# Lemming2_sensors.net
KiCad netlist of a schematic drawn in EAGLE
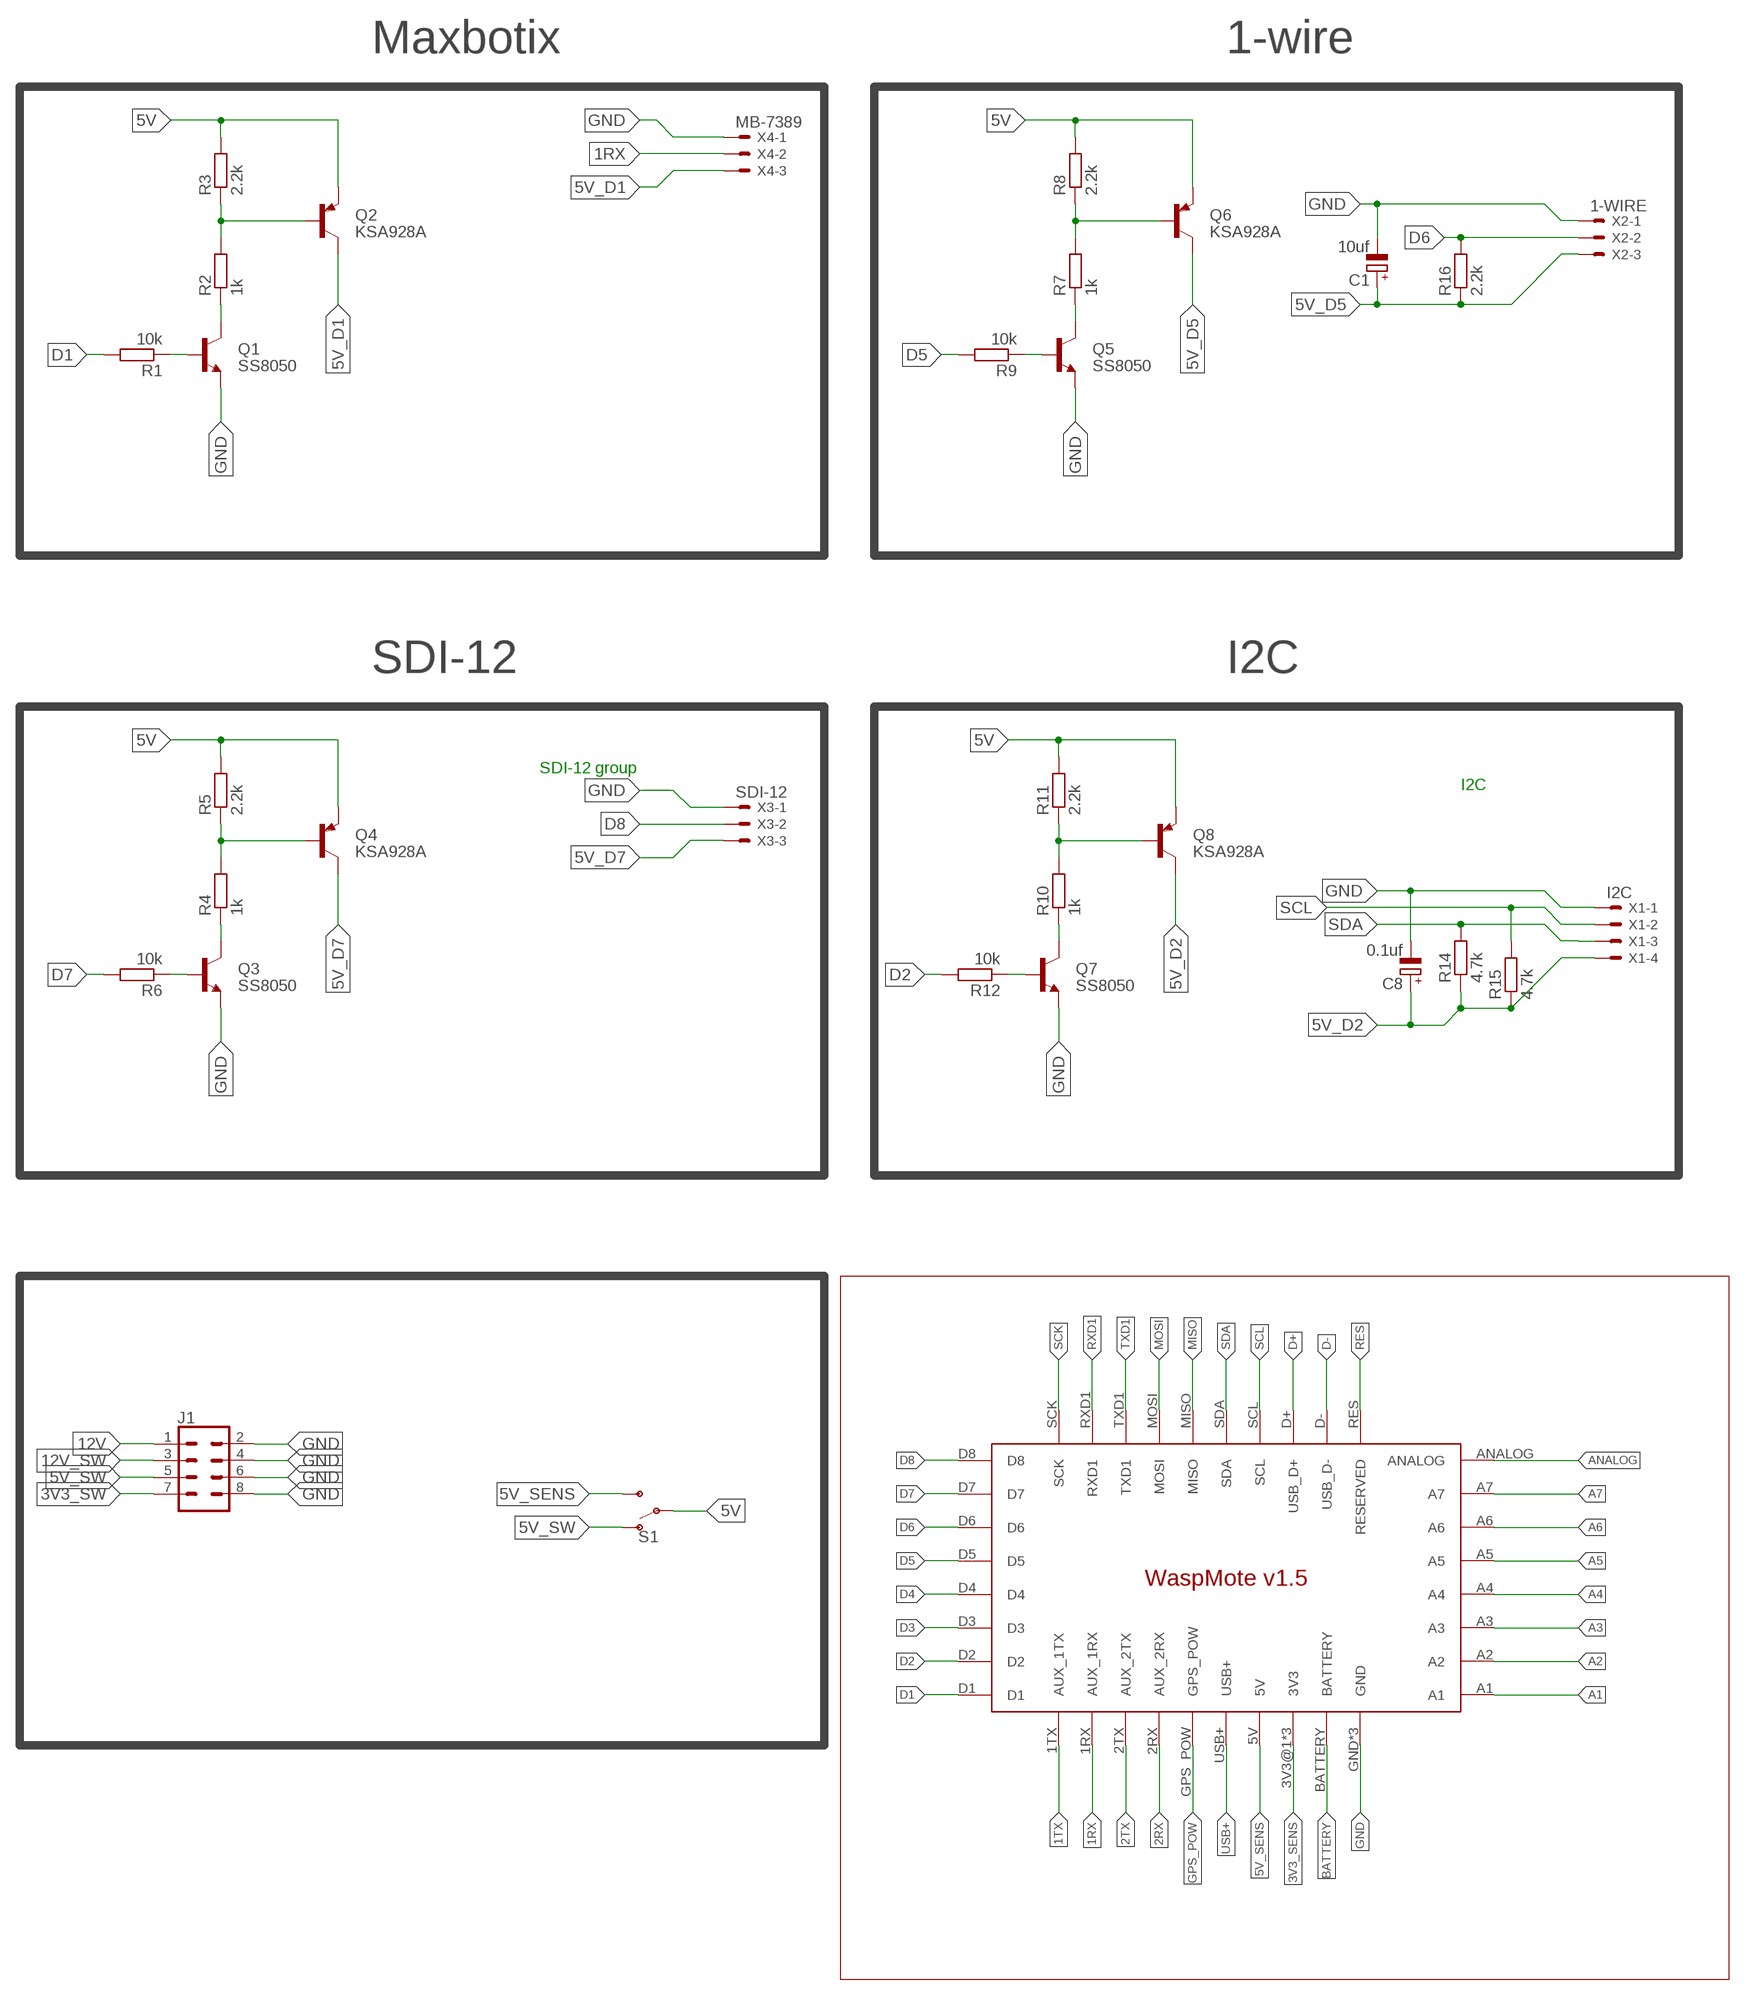
[diagram p0: schematic, sheet 1]

(export (version "E")
  (design (tool "Eeschema 10.0.6"))
  (components
    (comp (ref "C1")
      (value "10uf")
      (footprint "eagle-import:E2,5-5")
      (libsource (lib "eagle-import") (part "CPOL-EUE2.5-5"))
    )
    (comp (ref "C8")
      (value "0.1uf")
      (footprint "eagle-import:E2,5-5")
      (libsource (lib "eagle-import") (part "CPOL-EUE2.5-5"))
    )
    (comp (ref "J1")
      (value "CONN_04X2")
      (footprint "eagle-import:2X4")
      (libsource (lib "eagle-import") (part "CONN_04X2"))
    )
    (comp (ref "Q1")
      (value "SS8050")
      (footprint "eagle-import:TO-92-EBC")
      (libsource (lib "eagle-import") (part "SS8050"))
    )
    (comp (ref "Q2")
      (value "KSA928A")
      (footprint "eagle-import:TO-92-ECB")
      (libsource (lib "eagle-import") (part "KSA928A"))
    )
    (comp (ref "Q3")
      (value "SS8050")
      (footprint "eagle-import:TO-92-EBC")
      (libsource (lib "eagle-import") (part "SS8050"))
    )
    (comp (ref "Q4")
      (value "KSA928A")
      (footprint "eagle-import:TO-92-ECB")
      (libsource (lib "eagle-import") (part "KSA928A"))
    )
    (comp (ref "Q5")
      (value "SS8050")
      (footprint "eagle-import:TO-92-EBC")
      (libsource (lib "eagle-import") (part "SS8050"))
    )
    (comp (ref "Q6")
      (value "KSA928A")
      (footprint "eagle-import:TO-92-ECB")
      (libsource (lib "eagle-import") (part "KSA928A"))
    )
    (comp (ref "Q7")
      (value "SS8050")
      (footprint "eagle-import:TO-92-EBC")
      (libsource (lib "eagle-import") (part "SS8050"))
    )
    (comp (ref "Q8")
      (value "KSA928A")
      (footprint "eagle-import:TO-92-ECB")
      (libsource (lib "eagle-import") (part "KSA928A"))
    )
    (comp (ref "R1")
      (value "10k")
      (footprint "eagle-import:RESISTOR_0309_10")
      (libsource (lib "eagle-import") (part "RESISTOR_R-EU_0309/10"))
    )
    (comp (ref "R2")
      (value "1k")
      (footprint "eagle-import:RESISTOR_0309_10")
      (libsource (lib "eagle-import") (part "RESISTOR_R-EU_0309/10"))
    )
    (comp (ref "R3")
      (value "2.2k")
      (footprint "eagle-import:RESISTOR_0309_10")
      (libsource (lib "eagle-import") (part "RESISTOR_R-EU_0309/10"))
    )
    (comp (ref "R4")
      (value "1k")
      (footprint "eagle-import:RESISTOR_0309_10")
      (libsource (lib "eagle-import") (part "RESISTOR_R-EU_0309/10"))
    )
    (comp (ref "R5")
      (value "2.2k")
      (footprint "eagle-import:RESISTOR_0309_10")
      (libsource (lib "eagle-import") (part "RESISTOR_R-EU_0309/10"))
    )
    (comp (ref "R6")
      (value "10k")
      (footprint "eagle-import:RESISTOR_0309_10")
      (libsource (lib "eagle-import") (part "RESISTOR_R-EU_0309/10"))
    )
    (comp (ref "R7")
      (value "1k")
      (footprint "eagle-import:RESISTOR_0309_10")
      (libsource (lib "eagle-import") (part "RESISTOR_R-EU_0309/10"))
    )
    (comp (ref "R8")
      (value "2.2k")
      (footprint "eagle-import:RESISTOR_0309_10")
      (libsource (lib "eagle-import") (part "RESISTOR_R-EU_0309/10"))
    )
    (comp (ref "R9")
      (value "10k")
      (footprint "eagle-import:RESISTOR_0309_10")
      (libsource (lib "eagle-import") (part "RESISTOR_R-EU_0309/10"))
    )
    (comp (ref "R10")
      (value "1k")
      (footprint "eagle-import:RESISTOR_0309_10")
      (libsource (lib "eagle-import") (part "RESISTOR_R-EU_0309/10"))
    )
    (comp (ref "R11")
      (value "2.2k")
      (footprint "eagle-import:RESISTOR_0309_10")
      (libsource (lib "eagle-import") (part "RESISTOR_R-EU_0309/10"))
    )
    (comp (ref "R12")
      (value "10k")
      (footprint "eagle-import:RESISTOR_0309_10")
      (libsource (lib "eagle-import") (part "RESISTOR_R-EU_0309/10"))
    )
    (comp (ref "R14")
      (value "4.7k")
      (footprint "eagle-import:RESISTOR_0309_10")
      (libsource (lib "eagle-import") (part "RESISTOR_R-EU_0309/10"))
    )
    (comp (ref "R15")
      (value "4.7k")
      (footprint "eagle-import:RESISTOR_0309_10")
      (libsource (lib "eagle-import") (part "RESISTOR_R-EU_0309/10"))
    )
    (comp (ref "R16")
      (value "2.2k")
      (footprint "eagle-import:RESISTOR_0309_10")
      (libsource (lib "eagle-import") (part "RESISTOR_R-EU_0309/10"))
    )
    (comp (ref "S1")
      (value "SWITCH-SPDT-PTH-11.6X4.0MM")
      (footprint "eagle-import:SWITCH_SPDT_PTH_11.6X4.0MM")
      (libsource (lib "eagle-import") (part "SWITCH-SPDT-PTH-11.6X4.0MM"))
    )
    (comp (ref "U$1")
      (value "WASPMOTE_V1.5")
      (footprint "eagle-import:WASPMOTE_V1.5")
      (libsource (lib "eagle-import") (part "WASPMOTE_V1.5"))
    )
    (comp (ref "X1")
      (value "I2C")
      (footprint "eagle-import:22-23-2041")
      (fields (field (name "MF") "MOLEX") (field (name "MPN") "22-23-2041"))
      (libsource (lib "eagle-import") (part "22-23-2041"))
    )
    (comp (ref "X2")
      (value "1-WIRE")
      (footprint "eagle-import:22-23-2031")
      (fields (field (name "MF") "MOLEX") (field (name "MPN") "22-23-2031"))
      (libsource (lib "eagle-import") (part "22-23-2031"))
    )
    (comp (ref "X3")
      (value "SDI-12")
      (footprint "eagle-import:22-23-2031")
      (fields (field (name "MF") "MOLEX") (field (name "MPN") "22-23-2031"))
      (libsource (lib "eagle-import") (part "22-23-2031"))
    )
    (comp (ref "X4")
      (value "MB-7389")
      (footprint "eagle-import:22-23-2031")
      (fields (field (name "MF") "MOLEX") (field (name "MPN") "22-23-2031"))
      (libsource (lib "eagle-import") (part "22-23-2031"))
    )
  )
  (nets
    (net (code "1") (name "1RX") (class "Default")
      (node (ref "U$1") (pin "1RX") (pinfunction "AUX_1RX_1RX") (pintype "bidirectional"))
      (node (ref "X4") (pin "2") (pinfunction "S_2") (pintype "passive"))
    )
    (net (code "2") (name "1TX") (class "Default")
      (node (ref "U$1") (pin "1TX") (pinfunction "AUX_1TX_1TX") (pintype "bidirectional"))
    )
    (net (code "3") (name "2RX") (class "Default")
      (node (ref "U$1") (pin "2RX") (pinfunction "AUX_2RX_2RX") (pintype "bidirectional"))
    )
    (net (code "4") (name "2TX") (class "Default")
      (node (ref "U$1") (pin "2TX") (pinfunction "AUX_2TX_2TX") (pintype "bidirectional"))
    )
    (net (code "5") (name "3V3_SENS") (class "Default")
      (node (ref "U$1") (pin "3V3@1") (pinfunction "3V3_3V3@1") (pintype "bidirectional"))
      (node (ref "U$1") (pin "3V3@2") (pinfunction "3V3_3V3@2") (pintype "bidirectional"))
      (node (ref "U$1") (pin "3V3@3") (pinfunction "3V3_3V3@3") (pintype "bidirectional"))
    )
    (net (code "6") (name "3V3_SW") (class "Default")
      (node (ref "J1") (pin "7") (pinfunction "7_7") (pintype "passive"))
    )
    (net (code "7") (name "5V") (class "Default")
      (node (ref "Q2") (pin "E") (pinfunction "E_E") (pintype "passive"))
      (node (ref "Q4") (pin "E") (pinfunction "E_E") (pintype "passive"))
      (node (ref "Q6") (pin "E") (pinfunction "E_E") (pintype "passive"))
      (node (ref "Q8") (pin "E") (pinfunction "E_E") (pintype "passive"))
      (node (ref "R11") (pin "2") (pinfunction "2_2") (pintype "passive"))
      (node (ref "R3") (pin "2") (pinfunction "2_2") (pintype "passive"))
      (node (ref "R5") (pin "2") (pinfunction "2_2") (pintype "passive"))
      (node (ref "R8") (pin "2") (pinfunction "2_2") (pintype "passive"))
      (node (ref "S1") (pin "2") (pinfunction "P_2") (pintype "passive"))
    )
    (net (code "8") (name "5V_D1") (class "Default")
      (node (ref "Q2") (pin "C") (pinfunction "C_C") (pintype "passive"))
      (node (ref "X4") (pin "3") (pinfunction "S_3") (pintype "passive"))
    )
    (net (code "9") (name "5V_D2") (class "Default")
      (node (ref "C8") (pin "+") (pinfunction "+_+") (pintype "passive"))
      (node (ref "Q8") (pin "C") (pinfunction "C_C") (pintype "passive"))
      (node (ref "R14") (pin "1") (pinfunction "1_1") (pintype "passive"))
      (node (ref "R15") (pin "1") (pinfunction "1_1") (pintype "passive"))
      (node (ref "X1") (pin "4") (pinfunction "S_4") (pintype "passive"))
    )
    (net (code "10") (name "5V_D5") (class "Default")
      (node (ref "C1") (pin "+") (pinfunction "+_+") (pintype "passive"))
      (node (ref "Q6") (pin "C") (pinfunction "C_C") (pintype "passive"))
      (node (ref "R16") (pin "1") (pinfunction "1_1") (pintype "passive"))
      (node (ref "X2") (pin "3") (pinfunction "S_3") (pintype "passive"))
    )
    (net (code "11") (name "5V_D7") (class "Default")
      (node (ref "Q4") (pin "C") (pinfunction "C_C") (pintype "passive"))
      (node (ref "X3") (pin "3") (pinfunction "S_3") (pintype "passive"))
    )
    (net (code "12") (name "5V_SENS") (class "Default")
      (node (ref "S1") (pin "3") (pinfunction "S_3") (pintype "passive"))
      (node (ref "U$1") (pin "5V") (pinfunction "5V_5V") (pintype "bidirectional"))
    )
    (net (code "13") (name "5V_SW") (class "Default")
      (node (ref "J1") (pin "5") (pinfunction "5_5") (pintype "passive"))
      (node (ref "S1") (pin "1") (pinfunction "O_1") (pintype "passive"))
    )
    (net (code "14") (name "12V") (class "Default")
      (node (ref "J1") (pin "1") (pinfunction "1_1") (pintype "passive"))
    )
    (net (code "15") (name "12V_SW") (class "Default")
      (node (ref "J1") (pin "3") (pinfunction "3_3") (pintype "passive"))
    )
    (net (code "16") (name "A1") (class "Default")
      (node (ref "U$1") (pin "A1") (pinfunction "A1_A1") (pintype "bidirectional"))
    )
    (net (code "17") (name "A2") (class "Default")
      (node (ref "U$1") (pin "A2") (pinfunction "A2_A2") (pintype "bidirectional"))
    )
    (net (code "18") (name "A3") (class "Default")
      (node (ref "U$1") (pin "A3") (pinfunction "A3_A3") (pintype "bidirectional"))
    )
    (net (code "19") (name "A4") (class "Default")
      (node (ref "U$1") (pin "A4") (pinfunction "A4_A4") (pintype "bidirectional"))
    )
    (net (code "20") (name "A5") (class "Default")
      (node (ref "U$1") (pin "A5") (pinfunction "A5_A5") (pintype "bidirectional"))
    )
    (net (code "21") (name "A6") (class "Default")
      (node (ref "U$1") (pin "A6") (pinfunction "A6_A6") (pintype "bidirectional"))
    )
    (net (code "22") (name "A7") (class "Default")
      (node (ref "U$1") (pin "A7") (pinfunction "A7_A7") (pintype "bidirectional"))
    )
    (net (code "23") (name "ANALOG") (class "Default")
      (node (ref "U$1") (pin "ANALOG") (pinfunction "ANALOG_ANALOG") (pintype "bidirectional"))
    )
    (net (code "24") (name "BATTERY") (class "Default")
      (node (ref "U$1") (pin "BATTERY") (pinfunction "BATTERY_BATTERY") (pintype "bidirectional"))
    )
    (net (code "25") (name "D+") (class "Default")
      (node (ref "U$1") (pin "D+") (pinfunction "USB_D+_D+") (pintype "bidirectional"))
    )
    (net (code "26") (name "D-") (class "Default")
      (node (ref "U$1") (pin "D-") (pinfunction "USB_D-_D-") (pintype "bidirectional"))
    )
    (net (code "27") (name "D1") (class "Default")
      (node (ref "R1") (pin "2") (pinfunction "2_2") (pintype "passive"))
      (node (ref "U$1") (pin "D1") (pinfunction "D1_D1") (pintype "bidirectional"))
    )
    (net (code "28") (name "D2") (class "Default")
      (node (ref "R12") (pin "2") (pinfunction "2_2") (pintype "passive"))
      (node (ref "U$1") (pin "D2") (pinfunction "D2_D2") (pintype "bidirectional"))
    )
    (net (code "29") (name "D3") (class "Default")
      (node (ref "U$1") (pin "D3") (pinfunction "D3_D3") (pintype "bidirectional"))
    )
    (net (code "30") (name "D4") (class "Default")
      (node (ref "U$1") (pin "D4") (pinfunction "D4_D4") (pintype "bidirectional"))
    )
    (net (code "31") (name "D5") (class "Default")
      (node (ref "R9") (pin "2") (pinfunction "2_2") (pintype "passive"))
      (node (ref "U$1") (pin "D5") (pinfunction "D5_D5") (pintype "bidirectional"))
    )
    (net (code "32") (name "D6") (class "Default")
      (node (ref "R16") (pin "2") (pinfunction "2_2") (pintype "passive"))
      (node (ref "U$1") (pin "D6") (pinfunction "D6_D6") (pintype "bidirectional"))
      (node (ref "X2") (pin "2") (pinfunction "S_2") (pintype "passive"))
    )
    (net (code "33") (name "D7") (class "Default")
      (node (ref "R6") (pin "2") (pinfunction "2_2") (pintype "passive"))
      (node (ref "U$1") (pin "D7") (pinfunction "D7_D7") (pintype "bidirectional"))
    )
    (net (code "34") (name "D8") (class "Default")
      (node (ref "U$1") (pin "D8") (pinfunction "D8_D8") (pintype "bidirectional"))
      (node (ref "X3") (pin "2") (pinfunction "S_2") (pintype "passive"))
    )
    (net (code "35") (name "GND") (class "Default")
      (node (ref "C1") (pin "-") (pinfunction "-_-") (pintype "passive"))
      (node (ref "C8") (pin "-") (pinfunction "-_-") (pintype "passive"))
      (node (ref "J1") (pin "2") (pinfunction "2_2") (pintype "passive"))
      (node (ref "J1") (pin "4") (pinfunction "4_4") (pintype "passive"))
      (node (ref "J1") (pin "6") (pinfunction "6_6") (pintype "passive"))
      (node (ref "J1") (pin "8") (pinfunction "8_8") (pintype "passive"))
      (node (ref "Q1") (pin "E") (pinfunction "E_E") (pintype "passive"))
      (node (ref "Q3") (pin "E") (pinfunction "E_E") (pintype "passive"))
      (node (ref "Q5") (pin "E") (pinfunction "E_E") (pintype "passive"))
      (node (ref "Q7") (pin "E") (pinfunction "E_E") (pintype "passive"))
      (node (ref "U$1") (pin "GND") (pinfunction "GND_GND") (pintype "bidirectional"))
      (node (ref "U$1") (pin "GND_2") (pinfunction "GND_GND_2") (pintype "bidirectional"))
      (node (ref "U$1") (pin "USB-") (pinfunction "GND_USB-") (pintype "bidirectional"))
      (node (ref "X1") (pin "1") (pinfunction "S_1") (pintype "passive"))
      (node (ref "X2") (pin "1") (pinfunction "S_1") (pintype "passive"))
      (node (ref "X3") (pin "1") (pinfunction "S_1") (pintype "passive"))
      (node (ref "X4") (pin "1") (pinfunction "S_1") (pintype "passive"))
    )
    (net (code "36") (name "GPS_POW") (class "Default")
      (node (ref "U$1") (pin "GPS_POW") (pinfunction "GPS_POW_GPS_POW") (pintype "bidirectional"))
    )
    (net (code "37") (name "MISO") (class "Default")
      (node (ref "U$1") (pin "MISO") (pinfunction "MISO_MISO") (pintype "bidirectional"))
    )
    (net (code "38") (name "MOSI") (class "Default")
      (node (ref "U$1") (pin "MOSI") (pinfunction "MOSI_MOSI") (pintype "bidirectional"))
    )
    (net (code "39") (name "Net-(Q1-PadB)") (class "Default")
      (node (ref "Q1") (pin "B") (pinfunction "B_B") (pintype "passive"))
      (node (ref "R1") (pin "1") (pinfunction "1_1") (pintype "passive"))
    )
    (net (code "40") (name "Net-(Q1-PadC)") (class "Default")
      (node (ref "Q1") (pin "C") (pinfunction "C_C") (pintype "passive"))
      (node (ref "R2") (pin "1") (pinfunction "1_1") (pintype "passive"))
    )
    (net (code "41") (name "Net-(Q2-PadB)") (class "Default")
      (node (ref "Q2") (pin "B") (pinfunction "B_B") (pintype "passive"))
      (node (ref "R2") (pin "2") (pinfunction "2_2") (pintype "passive"))
      (node (ref "R3") (pin "1") (pinfunction "1_1") (pintype "passive"))
    )
    (net (code "42") (name "Net-(Q3-PadB)") (class "Default")
      (node (ref "Q3") (pin "B") (pinfunction "B_B") (pintype "passive"))
      (node (ref "R6") (pin "1") (pinfunction "1_1") (pintype "passive"))
    )
    (net (code "43") (name "Net-(Q3-PadC)") (class "Default")
      (node (ref "Q3") (pin "C") (pinfunction "C_C") (pintype "passive"))
      (node (ref "R4") (pin "1") (pinfunction "1_1") (pintype "passive"))
    )
    (net (code "44") (name "Net-(Q4-PadB)") (class "Default")
      (node (ref "Q4") (pin "B") (pinfunction "B_B") (pintype "passive"))
      (node (ref "R4") (pin "2") (pinfunction "2_2") (pintype "passive"))
      (node (ref "R5") (pin "1") (pinfunction "1_1") (pintype "passive"))
    )
    (net (code "45") (name "Net-(Q5-PadB)") (class "Default")
      (node (ref "Q5") (pin "B") (pinfunction "B_B") (pintype "passive"))
      (node (ref "R9") (pin "1") (pinfunction "1_1") (pintype "passive"))
    )
    (net (code "46") (name "Net-(Q5-PadC)") (class "Default")
      (node (ref "Q5") (pin "C") (pinfunction "C_C") (pintype "passive"))
      (node (ref "R7") (pin "1") (pinfunction "1_1") (pintype "passive"))
    )
    (net (code "47") (name "Net-(Q6-PadB)") (class "Default")
      (node (ref "Q6") (pin "B") (pinfunction "B_B") (pintype "passive"))
      (node (ref "R7") (pin "2") (pinfunction "2_2") (pintype "passive"))
      (node (ref "R8") (pin "1") (pinfunction "1_1") (pintype "passive"))
    )
    (net (code "48") (name "Net-(Q7-PadB)") (class "Default")
      (node (ref "Q7") (pin "B") (pinfunction "B_B") (pintype "passive"))
      (node (ref "R12") (pin "1") (pinfunction "1_1") (pintype "passive"))
    )
    (net (code "49") (name "Net-(Q7-PadC)") (class "Default")
      (node (ref "Q7") (pin "C") (pinfunction "C_C") (pintype "passive"))
      (node (ref "R10") (pin "1") (pinfunction "1_1") (pintype "passive"))
    )
    (net (code "50") (name "Net-(Q8-PadB)") (class "Default")
      (node (ref "Q8") (pin "B") (pinfunction "B_B") (pintype "passive"))
      (node (ref "R10") (pin "2") (pinfunction "2_2") (pintype "passive"))
      (node (ref "R11") (pin "1") (pinfunction "1_1") (pintype "passive"))
    )
    (net (code "51") (name "RES") (class "Default")
      (node (ref "U$1") (pin "RES") (pinfunction "RESERVED_RES") (pintype "bidirectional"))
    )
    (net (code "52") (name "RXD1") (class "Default")
      (node (ref "U$1") (pin "RXD1") (pinfunction "RXD1_RXD1") (pintype "bidirectional"))
    )
    (net (code "53") (name "SCK") (class "Default")
      (node (ref "U$1") (pin "SCK") (pinfunction "SCK_SCK") (pintype "bidirectional"))
    )
    (net (code "54") (name "SCL") (class "Default")
      (node (ref "R15") (pin "2") (pinfunction "2_2") (pintype "passive"))
      (node (ref "U$1") (pin "SCL") (pinfunction "SCL_SCL") (pintype "bidirectional"))
      (node (ref "X1") (pin "2") (pinfunction "S_2") (pintype "passive"))
    )
    (net (code "55") (name "SDA") (class "Default")
      (node (ref "R14") (pin "2") (pinfunction "2_2") (pintype "passive"))
      (node (ref "U$1") (pin "SDA") (pinfunction "SDA_SDA") (pintype "bidirectional"))
      (node (ref "X1") (pin "3") (pinfunction "S_3") (pintype "passive"))
    )
    (net (code "56") (name "TXD1") (class "Default")
      (node (ref "U$1") (pin "TXD1") (pinfunction "TXD1_TXD1") (pintype "bidirectional"))
    )
    (net (code "57") (name "USB+") (class "Default")
      (node (ref "U$1") (pin "USB+") (pinfunction "USB+_USB+") (pintype "bidirectional"))
    )
  )
)
